# rpi4pcie.net
KiCad netlist of a schematic drawn in EAGLE
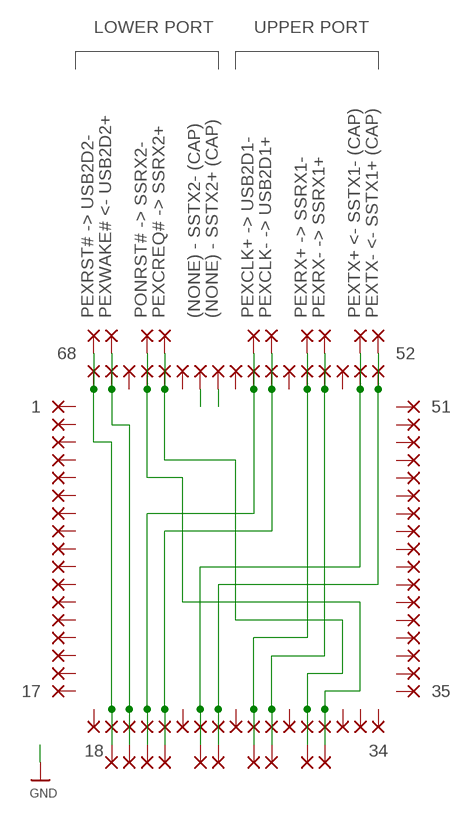
[diagram p0: schematic, sheet 1]

(export (version "E")
  (design (tool "Eeschema 10.0.6"))
  (components
    (comp (ref "PAD1")
      (value "PADQFN-0.4")
      (footprint "eagle-import:PAD-QFN-0.4")
      (libsource (lib "eagle-import") (part "PADQFN-0.4"))
    )
    (comp (ref "PAD2")
      (value "PADQFN-0.4")
      (footprint "eagle-import:PAD-QFN-0.4")
      (libsource (lib "eagle-import") (part "PADQFN-0.4"))
    )
    (comp (ref "PAD3")
      (value "PADQFN-0.4")
      (footprint "eagle-import:PAD-QFN-0.4")
      (libsource (lib "eagle-import") (part "PADQFN-0.4"))
    )
    (comp (ref "PAD4")
      (value "PADQFN-0.4")
      (footprint "eagle-import:PAD-QFN-0.4")
      (libsource (lib "eagle-import") (part "PADQFN-0.4"))
    )
    (comp (ref "PAD5")
      (value "PADQFN-0.4")
      (footprint "eagle-import:PAD-QFN-0.4")
      (libsource (lib "eagle-import") (part "PADQFN-0.4"))
    )
    (comp (ref "PAD6")
      (value "PADQFN-0.4")
      (footprint "eagle-import:PAD-QFN-0.4")
      (libsource (lib "eagle-import") (part "PADQFN-0.4"))
    )
    (comp (ref "PAD7")
      (value "PADQFN-0.4")
      (footprint "eagle-import:PAD-QFN-0.4")
      (libsource (lib "eagle-import") (part "PADQFN-0.4"))
    )
    (comp (ref "PAD8")
      (value "PADQFN-0.4")
      (footprint "eagle-import:PAD-QFN-0.4")
      (libsource (lib "eagle-import") (part "PADQFN-0.4"))
    )
    (comp (ref "PAD9")
      (value "PADQFN-0.4")
      (footprint "eagle-import:PAD-QFN-0.4")
      (libsource (lib "eagle-import") (part "PADQFN-0.4"))
    )
    (comp (ref "PAD10")
      (value "PADQFN-0.4")
      (footprint "eagle-import:PAD-QFN-0.4")
      (libsource (lib "eagle-import") (part "PADQFN-0.4"))
    )
    (comp (ref "PAD11")
      (value "PADQFN-0.4")
      (footprint "eagle-import:PAD-QFN-0.4")
      (libsource (lib "eagle-import") (part "PADQFN-0.4"))
    )
    (comp (ref "PAD12")
      (value "PADQFN-0.4")
      (footprint "eagle-import:PAD-QFN-0.4")
      (libsource (lib "eagle-import") (part "PADQFN-0.4"))
    )
    (comp (ref "PAD13")
      (value "PADQFN-0.4")
      (footprint "eagle-import:PAD-QFN-0.4")
      (libsource (lib "eagle-import") (part "PADQFN-0.4"))
    )
    (comp (ref "PAD14")
      (value "PADQFN-0.4")
      (footprint "eagle-import:PAD-QFN-0.4")
      (libsource (lib "eagle-import") (part "PADQFN-0.4"))
    )
    (comp (ref "PAD15")
      (value "PADQFN-0.4")
      (footprint "eagle-import:PAD-QFN-0.4")
      (libsource (lib "eagle-import") (part "PADQFN-0.4"))
    )
    (comp (ref "PAD16")
      (value "PADQFN-0.4")
      (footprint "eagle-import:PAD-QFN-0.4")
      (libsource (lib "eagle-import") (part "PADQFN-0.4"))
    )
    (comp (ref "PAD17")
      (value "PADQFN-0.4")
      (footprint "eagle-import:PAD-QFN-0.4")
      (libsource (lib "eagle-import") (part "PADQFN-0.4"))
    )
    (comp (ref "PAD18")
      (value "PADQFN-0.4")
      (footprint "eagle-import:PAD-QFN-0.4")
      (libsource (lib "eagle-import") (part "PADQFN-0.4"))
    )
    (comp (ref "PAD19")
      (value "PADQFN-0.4")
      (footprint "eagle-import:PAD-QFN-0.4")
      (libsource (lib "eagle-import") (part "PADQFN-0.4"))
    )
    (comp (ref "PAD20")
      (value "PADQFN-0.4")
      (footprint "eagle-import:PAD-QFN-0.4")
      (libsource (lib "eagle-import") (part "PADQFN-0.4"))
    )
    (comp (ref "PAD21")
      (value "PADQFN-0.4")
      (footprint "eagle-import:PAD-QFN-0.4")
      (libsource (lib "eagle-import") (part "PADQFN-0.4"))
    )
    (comp (ref "PAD22")
      (value "PADQFN-0.4")
      (footprint "eagle-import:PAD-QFN-0.4")
      (libsource (lib "eagle-import") (part "PADQFN-0.4"))
    )
    (comp (ref "PAD23")
      (value "PADQFN-0.4")
      (footprint "eagle-import:PAD-QFN-0.4")
      (libsource (lib "eagle-import") (part "PADQFN-0.4"))
    )
    (comp (ref "PAD24")
      (value "PADQFN-0.4")
      (footprint "eagle-import:PAD-QFN-0.4")
      (libsource (lib "eagle-import") (part "PADQFN-0.4"))
    )
    (comp (ref "PAD25")
      (value "PADQFN-0.4")
      (footprint "eagle-import:PAD-QFN-0.4")
      (libsource (lib "eagle-import") (part "PADQFN-0.4"))
    )
    (comp (ref "PAD26")
      (value "PADQFN-0.4")
      (footprint "eagle-import:PAD-QFN-0.4")
      (libsource (lib "eagle-import") (part "PADQFN-0.4"))
    )
    (comp (ref "PAD27")
      (value "PADQFN-0.4")
      (footprint "eagle-import:PAD-QFN-0.4")
      (libsource (lib "eagle-import") (part "PADQFN-0.4"))
    )
    (comp (ref "PAD28")
      (value "PADQFN-0.4")
      (footprint "eagle-import:PAD-QFN-0.4")
      (libsource (lib "eagle-import") (part "PADQFN-0.4"))
    )
    (comp (ref "PAD29")
      (value "PADQFN-0.4")
      (footprint "eagle-import:PAD-QFN-0.4")
      (libsource (lib "eagle-import") (part "PADQFN-0.4"))
    )
    (comp (ref "PAD30")
      (value "PADQFN-0.4")
      (footprint "eagle-import:PAD-QFN-0.4")
      (libsource (lib "eagle-import") (part "PADQFN-0.4"))
    )
    (comp (ref "PAD31")
      (value "PADQFN-0.4")
      (footprint "eagle-import:PAD-QFN-0.4")
      (libsource (lib "eagle-import") (part "PADQFN-0.4"))
    )
    (comp (ref "PAD32")
      (value "PADQFN-0.4")
      (footprint "eagle-import:PAD-QFN-0.4")
      (libsource (lib "eagle-import") (part "PADQFN-0.4"))
    )
    (comp (ref "PAD33")
      (value "PADQFN-0.4")
      (footprint "eagle-import:PAD-QFN-0.4")
      (libsource (lib "eagle-import") (part "PADQFN-0.4"))
    )
    (comp (ref "PAD34")
      (value "PADQFN-0.4")
      (footprint "eagle-import:PAD-QFN-0.4")
      (libsource (lib "eagle-import") (part "PADQFN-0.4"))
    )
    (comp (ref "PAD35")
      (value "PADQFN-0.4")
      (footprint "eagle-import:PAD-QFN-0.4")
      (libsource (lib "eagle-import") (part "PADQFN-0.4"))
    )
    (comp (ref "PAD36")
      (value "PADQFN-0.4")
      (footprint "eagle-import:PAD-QFN-0.4")
      (libsource (lib "eagle-import") (part "PADQFN-0.4"))
    )
    (comp (ref "PAD37")
      (value "PADQFN-0.4")
      (footprint "eagle-import:PAD-QFN-0.4")
      (libsource (lib "eagle-import") (part "PADQFN-0.4"))
    )
    (comp (ref "PAD38")
      (value "PADQFN-0.4")
      (footprint "eagle-import:PAD-QFN-0.4")
      (libsource (lib "eagle-import") (part "PADQFN-0.4"))
    )
    (comp (ref "PAD39")
      (value "PADQFN-0.4")
      (footprint "eagle-import:PAD-QFN-0.4")
      (libsource (lib "eagle-import") (part "PADQFN-0.4"))
    )
    (comp (ref "PAD40")
      (value "PADQFN-0.4")
      (footprint "eagle-import:PAD-QFN-0.4")
      (libsource (lib "eagle-import") (part "PADQFN-0.4"))
    )
    (comp (ref "PAD41")
      (value "PADQFN-0.4")
      (footprint "eagle-import:PAD-QFN-0.4")
      (libsource (lib "eagle-import") (part "PADQFN-0.4"))
    )
    (comp (ref "PAD42")
      (value "PADQFN-0.4")
      (footprint "eagle-import:PAD-QFN-0.4")
      (libsource (lib "eagle-import") (part "PADQFN-0.4"))
    )
    (comp (ref "PAD43")
      (value "PADQFN-0.4")
      (footprint "eagle-import:PAD-QFN-0.4")
      (libsource (lib "eagle-import") (part "PADQFN-0.4"))
    )
    (comp (ref "PAD44")
      (value "PADQFN-0.4")
      (footprint "eagle-import:PAD-QFN-0.4")
      (libsource (lib "eagle-import") (part "PADQFN-0.4"))
    )
    (comp (ref "PAD45")
      (value "PADQFN-0.4")
      (footprint "eagle-import:PAD-QFN-0.4")
      (libsource (lib "eagle-import") (part "PADQFN-0.4"))
    )
    (comp (ref "PAD46")
      (value "PADQFN-0.4")
      (footprint "eagle-import:PAD-QFN-0.4")
      (libsource (lib "eagle-import") (part "PADQFN-0.4"))
    )
    (comp (ref "PAD47")
      (value "PADQFN-0.4")
      (footprint "eagle-import:PAD-QFN-0.4")
      (libsource (lib "eagle-import") (part "PADQFN-0.4"))
    )
    (comp (ref "PAD48")
      (value "PADQFN-0.4")
      (footprint "eagle-import:PAD-QFN-0.4")
      (libsource (lib "eagle-import") (part "PADQFN-0.4"))
    )
    (comp (ref "PAD49")
      (value "PADQFN-0.4")
      (footprint "eagle-import:PAD-QFN-0.4")
      (libsource (lib "eagle-import") (part "PADQFN-0.4"))
    )
    (comp (ref "PAD50")
      (value "PADQFN-0.4")
      (footprint "eagle-import:PAD-QFN-0.4")
      (libsource (lib "eagle-import") (part "PADQFN-0.4"))
    )
    (comp (ref "PAD51")
      (value "PADQFN-0.4")
      (footprint "eagle-import:PAD-QFN-0.4")
      (libsource (lib "eagle-import") (part "PADQFN-0.4"))
    )
    (comp (ref "PAD52")
      (value "PADQFN-0.4")
      (footprint "eagle-import:PAD-QFN-0.4")
      (libsource (lib "eagle-import") (part "PADQFN-0.4"))
    )
    (comp (ref "PAD53")
      (value "PADQFN-0.4")
      (footprint "eagle-import:PAD-QFN-0.4")
      (libsource (lib "eagle-import") (part "PADQFN-0.4"))
    )
    (comp (ref "PAD54")
      (value "PADQFN-0.4")
      (footprint "eagle-import:PAD-QFN-0.4")
      (libsource (lib "eagle-import") (part "PADQFN-0.4"))
    )
    (comp (ref "PAD55")
      (value "PADQFN-0.4")
      (footprint "eagle-import:PAD-QFN-0.4")
      (libsource (lib "eagle-import") (part "PADQFN-0.4"))
    )
    (comp (ref "PAD56")
      (value "PADQFN-0.4")
      (footprint "eagle-import:PAD-QFN-0.4")
      (libsource (lib "eagle-import") (part "PADQFN-0.4"))
    )
    (comp (ref "PAD57")
      (value "PADQFN-0.4")
      (footprint "eagle-import:PAD-QFN-0.4")
      (libsource (lib "eagle-import") (part "PADQFN-0.4"))
    )
    (comp (ref "PAD58")
      (value "PADQFN-0.4")
      (footprint "eagle-import:PAD-QFN-0.4")
      (libsource (lib "eagle-import") (part "PADQFN-0.4"))
    )
    (comp (ref "PAD59")
      (value "PADQFN-0.4")
      (footprint "eagle-import:PAD-QFN-0.4")
      (libsource (lib "eagle-import") (part "PADQFN-0.4"))
    )
    (comp (ref "PAD60")
      (value "PADQFN-0.4")
      (footprint "eagle-import:PAD-QFN-0.4")
      (libsource (lib "eagle-import") (part "PADQFN-0.4"))
    )
    (comp (ref "PAD61")
      (value "PADQFN-0.4")
      (footprint "eagle-import:PAD-QFN-0.4")
      (libsource (lib "eagle-import") (part "PADQFN-0.4"))
    )
    (comp (ref "PAD62")
      (value "PADQFN-0.4")
      (footprint "eagle-import:PAD-QFN-0.4")
      (libsource (lib "eagle-import") (part "PADQFN-0.4"))
    )
    (comp (ref "PAD63")
      (value "PADQFN-0.4")
      (footprint "eagle-import:PAD-QFN-0.4")
      (libsource (lib "eagle-import") (part "PADQFN-0.4"))
    )
    (comp (ref "PAD64")
      (value "PADQFN-0.4")
      (footprint "eagle-import:PAD-QFN-0.4")
      (libsource (lib "eagle-import") (part "PADQFN-0.4"))
    )
    (comp (ref "PAD65")
      (value "PADQFN-0.4")
      (footprint "eagle-import:PAD-QFN-0.4")
      (libsource (lib "eagle-import") (part "PADQFN-0.4"))
    )
    (comp (ref "PAD66")
      (value "PADQFN-0.4")
      (footprint "eagle-import:PAD-QFN-0.4")
      (libsource (lib "eagle-import") (part "PADQFN-0.4"))
    )
    (comp (ref "PAD67")
      (value "PADQFN-0.4")
      (footprint "eagle-import:PAD-QFN-0.4")
      (libsource (lib "eagle-import") (part "PADQFN-0.4"))
    )
    (comp (ref "PAD68")
      (value "PADQFN-0.4")
      (footprint "eagle-import:PAD-QFN-0.4")
      (libsource (lib "eagle-import") (part "PADQFN-0.4"))
    )
    (comp (ref "PAD69")
      (value "PADQFN-0.4")
      (footprint "eagle-import:PAD-QFN-0.4")
      (libsource (lib "eagle-import") (part "PADQFN-0.4"))
    )
    (comp (ref "PAD70")
      (value "PADQFN-0.4")
      (footprint "eagle-import:PAD-QFN-0.4")
      (libsource (lib "eagle-import") (part "PADQFN-0.4"))
    )
    (comp (ref "PAD71")
      (value "PADQFN-0.4")
      (footprint "eagle-import:PAD-QFN-0.4")
      (libsource (lib "eagle-import") (part "PADQFN-0.4"))
    )
    (comp (ref "PAD72")
      (value "PADQFN-0.4")
      (footprint "eagle-import:PAD-QFN-0.4")
      (libsource (lib "eagle-import") (part "PADQFN-0.4"))
    )
    (comp (ref "PAD73")
      (value "PADQFN-0.4")
      (footprint "eagle-import:PAD-QFN-0.4")
      (libsource (lib "eagle-import") (part "PADQFN-0.4"))
    )
    (comp (ref "PAD74")
      (value "PADQFN-0.4")
      (footprint "eagle-import:PAD-QFN-0.4")
      (libsource (lib "eagle-import") (part "PADQFN-0.4"))
    )
    (comp (ref "PAD75")
      (value "PADQFN-0.4")
      (footprint "eagle-import:PAD-QFN-0.4")
      (libsource (lib "eagle-import") (part "PADQFN-0.4"))
    )
    (comp (ref "PAD76")
      (value "PADQFN-0.4")
      (footprint "eagle-import:PAD-QFN-0.4")
      (libsource (lib "eagle-import") (part "PADQFN-0.4"))
    )
    (comp (ref "PAD77")
      (value "PADQFN-0.4")
      (footprint "eagle-import:PAD-QFN-0.4")
      (libsource (lib "eagle-import") (part "PADQFN-0.4"))
    )
    (comp (ref "PAD78")
      (value "PADQFN-0.4")
      (footprint "eagle-import:PAD-QFN-0.4")
      (libsource (lib "eagle-import") (part "PADQFN-0.4"))
    )
    (comp (ref "PAD79")
      (value "PADQFN-0.4")
      (footprint "eagle-import:PAD-QFN-0.4")
      (libsource (lib "eagle-import") (part "PADQFN-0.4"))
    )
    (comp (ref "PAD80")
      (value "PADQFN-0.4")
      (footprint "eagle-import:PAD-QFN-0.4")
      (libsource (lib "eagle-import") (part "PADQFN-0.4"))
    )
    (comp (ref "PAD81")
      (value "PADQFN-0.4")
      (footprint "eagle-import:PAD-QFN-0.4")
      (libsource (lib "eagle-import") (part "PADQFN-0.4"))
    )
    (comp (ref "PAD82")
      (value "PADQFN-0.4")
      (footprint "eagle-import:PAD-QFN-0.4")
      (libsource (lib "eagle-import") (part "PADQFN-0.4"))
    )
    (comp (ref "PAD83")
      (value "PADQFN-0.4")
      (footprint "eagle-import:PAD-QFN-0.4")
      (libsource (lib "eagle-import") (part "PADQFN-0.4"))
    )
    (comp (ref "PAD84")
      (value "PADQFN-0.4")
      (footprint "eagle-import:PAD-QFN-0.4")
      (libsource (lib "eagle-import") (part "PADQFN-0.4"))
    )
    (comp (ref "PAD85")
      (value "PADQFN-0.4")
      (footprint "eagle-import:PAD-QFN-0.4")
      (libsource (lib "eagle-import") (part "PADQFN-0.4"))
    )
    (comp (ref "PAD86")
      (value "PADQFN-0.4")
      (footprint "eagle-import:PAD-QFN-0.4")
      (libsource (lib "eagle-import") (part "PADQFN-0.4"))
    )
    (comp (ref "PAD87")
      (value "PADQFN-0.4")
      (footprint "eagle-import:PAD-QFN-0.4")
      (libsource (lib "eagle-import") (part "PADQFN-0.4"))
    )
    (comp (ref "PAD88")
      (value "PADQFN-0.4")
      (footprint "eagle-import:PAD-QFN-0.4")
      (libsource (lib "eagle-import") (part "PADQFN-0.4"))
    )
  )
  (nets
    (net (code "2") (name "Net-(PAD19-P$1)") (class "Default")
      (node (ref "PAD19") (pin "1") (pinfunction "P$1_1") (pintype "passive"))
      (node (ref "PAD68") (pin "1") (pinfunction "P$1_1") (pintype "passive"))
      (node (ref "PAD69") (pin "1") (pinfunction "P$1_1") (pintype "passive"))
      (node (ref "PAD77") (pin "1") (pinfunction "P$1_1") (pintype "passive"))
    )
    (net (code "3") (name "Net-(PAD20-P$1)") (class "Default")
      (node (ref "PAD20") (pin "1") (pinfunction "P$1_1") (pintype "passive"))
      (node (ref "PAD67") (pin "1") (pinfunction "P$1_1") (pintype "passive"))
      (node (ref "PAD70") (pin "1") (pinfunction "P$1_1") (pintype "passive"))
      (node (ref "PAD78") (pin "1") (pinfunction "P$1_1") (pintype "passive"))
    )
    (net (code "4") (name "Net-(PAD21-P$1)") (class "Default")
      (node (ref "PAD21") (pin "1") (pinfunction "P$1_1") (pintype "passive"))
      (node (ref "PAD59") (pin "1") (pinfunction "P$1_1") (pintype "passive"))
      (node (ref "PAD71") (pin "1") (pinfunction "P$1_1") (pintype "passive"))
      (node (ref "PAD79") (pin "1") (pinfunction "P$1_1") (pintype "passive"))
    )
    (net (code "5") (name "Net-(PAD22-P$1)") (class "Default")
      (node (ref "PAD22") (pin "1") (pinfunction "P$1_1") (pintype "passive"))
      (node (ref "PAD58") (pin "1") (pinfunction "P$1_1") (pintype "passive"))
      (node (ref "PAD72") (pin "1") (pinfunction "P$1_1") (pintype "passive"))
      (node (ref "PAD80") (pin "1") (pinfunction "P$1_1") (pintype "passive"))
    )
    (net (code "6") (name "Net-(PAD24-P$1)") (class "Default")
      (node (ref "PAD24") (pin "1") (pinfunction "P$1_1") (pintype "passive"))
      (node (ref "PAD53") (pin "1") (pinfunction "P$1_1") (pintype "passive"))
      (node (ref "PAD75") (pin "1") (pinfunction "P$1_1") (pintype "passive"))
      (node (ref "PAD81") (pin "1") (pinfunction "P$1_1") (pintype "passive"))
    )
    (net (code "7") (name "Net-(PAD25-P$1)") (class "Default")
      (node (ref "PAD25") (pin "1") (pinfunction "P$1_1") (pintype "passive"))
      (node (ref "PAD52") (pin "1") (pinfunction "P$1_1") (pintype "passive"))
      (node (ref "PAD76") (pin "1") (pinfunction "P$1_1") (pintype "passive"))
      (node (ref "PAD82") (pin "1") (pinfunction "P$1_1") (pintype "passive"))
    )
    (net (code "8") (name "Net-(PAD27-P$1)") (class "Default")
      (node (ref "PAD27") (pin "1") (pinfunction "P$1_1") (pintype "passive"))
      (node (ref "PAD56") (pin "1") (pinfunction "P$1_1") (pintype "passive"))
      (node (ref "PAD73") (pin "1") (pinfunction "P$1_1") (pintype "passive"))
      (node (ref "PAD83") (pin "1") (pinfunction "P$1_1") (pintype "passive"))
    )
    (net (code "9") (name "Net-(PAD28-P$1)") (class "Default")
      (node (ref "PAD28") (pin "1") (pinfunction "P$1_1") (pintype "passive"))
      (node (ref "PAD55") (pin "1") (pinfunction "P$1_1") (pintype "passive"))
      (node (ref "PAD74") (pin "1") (pinfunction "P$1_1") (pintype "passive"))
      (node (ref "PAD84") (pin "1") (pinfunction "P$1_1") (pintype "passive"))
    )
    (net (code "10") (name "Net-(PAD30-P$1)") (class "Default")
      (node (ref "PAD30") (pin "1") (pinfunction "P$1_1") (pintype "passive"))
      (node (ref "PAD64") (pin "1") (pinfunction "P$1_1") (pintype "passive"))
      (node (ref "PAD85") (pin "1") (pinfunction "P$1_1") (pintype "passive"))
      (node (ref "PAD88") (pin "1") (pinfunction "P$1_1") (pintype "passive"))
    )
    (net (code "11") (name "Net-(PAD31-P$1)") (class "Default")
      (node (ref "PAD31") (pin "1") (pinfunction "P$1_1") (pintype "passive"))
      (node (ref "PAD65") (pin "1") (pinfunction "P$1_1") (pintype "passive"))
      (node (ref "PAD86") (pin "1") (pinfunction "P$1_1") (pintype "passive"))
      (node (ref "PAD87") (pin "1") (pinfunction "P$1_1") (pintype "passive"))
    )
    (net (code "12") (name "unconnected-(PAD1-P$1-Pad1)") (class "Default")
      (node (ref "PAD1") (pin "1") (pinfunction "P$1_1") (pintype "passive"))
    )
    (net (code "13") (name "unconnected-(PAD2-P$1-Pad1)") (class "Default")
      (node (ref "PAD2") (pin "1") (pinfunction "P$1_1") (pintype "passive"))
    )
    (net (code "14") (name "unconnected-(PAD3-P$1-Pad1)") (class "Default")
      (node (ref "PAD3") (pin "1") (pinfunction "P$1_1") (pintype "passive"))
    )
    (net (code "15") (name "unconnected-(PAD4-P$1-Pad1)") (class "Default")
      (node (ref "PAD4") (pin "1") (pinfunction "P$1_1") (pintype "passive"))
    )
    (net (code "16") (name "unconnected-(PAD5-P$1-Pad1)") (class "Default")
      (node (ref "PAD5") (pin "1") (pinfunction "P$1_1") (pintype "passive"))
    )
    (net (code "17") (name "unconnected-(PAD6-P$1-Pad1)") (class "Default")
      (node (ref "PAD6") (pin "1") (pinfunction "P$1_1") (pintype "passive"))
    )
    (net (code "18") (name "unconnected-(PAD7-P$1-Pad1)") (class "Default")
      (node (ref "PAD7") (pin "1") (pinfunction "P$1_1") (pintype "passive"))
    )
    (net (code "19") (name "unconnected-(PAD8-P$1-Pad1)") (class "Default")
      (node (ref "PAD8") (pin "1") (pinfunction "P$1_1") (pintype "passive"))
    )
    (net (code "20") (name "unconnected-(PAD9-P$1-Pad1)") (class "Default")
      (node (ref "PAD9") (pin "1") (pinfunction "P$1_1") (pintype "passive"))
    )
    (net (code "21") (name "unconnected-(PAD10-P$1-Pad1)") (class "Default")
      (node (ref "PAD10") (pin "1") (pinfunction "P$1_1") (pintype "passive"))
    )
    (net (code "22") (name "unconnected-(PAD11-P$1-Pad1)") (class "Default")
      (node (ref "PAD11") (pin "1") (pinfunction "P$1_1") (pintype "passive"))
    )
    (net (code "23") (name "unconnected-(PAD12-P$1-Pad1)") (class "Default")
      (node (ref "PAD12") (pin "1") (pinfunction "P$1_1") (pintype "passive"))
    )
    (net (code "24") (name "unconnected-(PAD13-P$1-Pad1)") (class "Default")
      (node (ref "PAD13") (pin "1") (pinfunction "P$1_1") (pintype "passive"))
    )
    (net (code "25") (name "unconnected-(PAD14-P$1-Pad1)") (class "Default")
      (node (ref "PAD14") (pin "1") (pinfunction "P$1_1") (pintype "passive"))
    )
    (net (code "26") (name "unconnected-(PAD15-P$1-Pad1)") (class "Default")
      (node (ref "PAD15") (pin "1") (pinfunction "P$1_1") (pintype "passive"))
    )
    (net (code "27") (name "unconnected-(PAD16-P$1-Pad1)") (class "Default")
      (node (ref "PAD16") (pin "1") (pinfunction "P$1_1") (pintype "passive"))
    )
    (net (code "28") (name "unconnected-(PAD17-P$1-Pad1)") (class "Default")
      (node (ref "PAD17") (pin "1") (pinfunction "P$1_1") (pintype "passive"))
    )
    (net (code "29") (name "unconnected-(PAD18-P$1-Pad1)") (class "Default")
      (node (ref "PAD18") (pin "1") (pinfunction "P$1_1") (pintype "passive"))
    )
    (net (code "30") (name "unconnected-(PAD23-P$1-Pad1)") (class "Default")
      (node (ref "PAD23") (pin "1") (pinfunction "P$1_1") (pintype "passive"))
    )
    (net (code "31") (name "unconnected-(PAD26-P$1-Pad1)") (class "Default")
      (node (ref "PAD26") (pin "1") (pinfunction "P$1_1") (pintype "passive"))
    )
    (net (code "32") (name "unconnected-(PAD29-P$1-Pad1)") (class "Default")
      (node (ref "PAD29") (pin "1") (pinfunction "P$1_1") (pintype "passive"))
    )
    (net (code "33") (name "unconnected-(PAD32-P$1-Pad1)") (class "Default")
      (node (ref "PAD32") (pin "1") (pinfunction "P$1_1") (pintype "passive"))
    )
    (net (code "34") (name "unconnected-(PAD33-P$1-Pad1)") (class "Default")
      (node (ref "PAD33") (pin "1") (pinfunction "P$1_1") (pintype "passive"))
    )
    (net (code "35") (name "unconnected-(PAD34-P$1-Pad1)") (class "Default")
      (node (ref "PAD34") (pin "1") (pinfunction "P$1_1") (pintype "passive"))
    )
    (net (code "36") (name "unconnected-(PAD35-P$1-Pad1)") (class "Default")
      (node (ref "PAD35") (pin "1") (pinfunction "P$1_1") (pintype "passive"))
    )
    (net (code "37") (name "unconnected-(PAD36-P$1-Pad1)") (class "Default")
      (node (ref "PAD36") (pin "1") (pinfunction "P$1_1") (pintype "passive"))
    )
    (net (code "38") (name "unconnected-(PAD37-P$1-Pad1)") (class "Default")
      (node (ref "PAD37") (pin "1") (pinfunction "P$1_1") (pintype "passive"))
    )
    (net (code "39") (name "unconnected-(PAD38-P$1-Pad1)") (class "Default")
      (node (ref "PAD38") (pin "1") (pinfunction "P$1_1") (pintype "passive"))
    )
    (net (code "40") (name "unconnected-(PAD39-P$1-Pad1)") (class "Default")
      (node (ref "PAD39") (pin "1") (pinfunction "P$1_1") (pintype "passive"))
    )
    (net (code "41") (name "unconnected-(PAD40-P$1-Pad1)") (class "Default")
      (node (ref "PAD40") (pin "1") (pinfunction "P$1_1") (pintype "passive"))
    )
    (net (code "42") (name "unconnected-(PAD41-P$1-Pad1)") (class "Default")
      (node (ref "PAD41") (pin "1") (pinfunction "P$1_1") (pintype "passive"))
    )
    (net (code "43") (name "unconnected-(PAD42-P$1-Pad1)") (class "Default")
      (node (ref "PAD42") (pin "1") (pinfunction "P$1_1") (pintype "passive"))
    )
    (net (code "44") (name "unconnected-(PAD43-P$1-Pad1)") (class "Default")
      (node (ref "PAD43") (pin "1") (pinfunction "P$1_1") (pintype "passive"))
    )
    (net (code "45") (name "unconnected-(PAD44-P$1-Pad1)") (class "Default")
      (node (ref "PAD44") (pin "1") (pinfunction "P$1_1") (pintype "passive"))
    )
    (net (code "46") (name "unconnected-(PAD45-P$1-Pad1)") (class "Default")
      (node (ref "PAD45") (pin "1") (pinfunction "P$1_1") (pintype "passive"))
    )
    (net (code "47") (name "unconnected-(PAD46-P$1-Pad1)") (class "Default")
      (node (ref "PAD46") (pin "1") (pinfunction "P$1_1") (pintype "passive"))
    )
    (net (code "48") (name "unconnected-(PAD47-P$1-Pad1)") (class "Default")
      (node (ref "PAD47") (pin "1") (pinfunction "P$1_1") (pintype "passive"))
    )
    (net (code "49") (name "unconnected-(PAD48-P$1-Pad1)") (class "Default")
      (node (ref "PAD48") (pin "1") (pinfunction "P$1_1") (pintype "passive"))
    )
    (net (code "50") (name "unconnected-(PAD49-P$1-Pad1)") (class "Default")
      (node (ref "PAD49") (pin "1") (pinfunction "P$1_1") (pintype "passive"))
    )
    (net (code "51") (name "unconnected-(PAD50-P$1-Pad1)") (class "Default")
      (node (ref "PAD50") (pin "1") (pinfunction "P$1_1") (pintype "passive"))
    )
    (net (code "52") (name "unconnected-(PAD51-P$1-Pad1)") (class "Default")
      (node (ref "PAD51") (pin "1") (pinfunction "P$1_1") (pintype "passive"))
    )
    (net (code "53") (name "unconnected-(PAD54-P$1-Pad1)") (class "Default")
      (node (ref "PAD54") (pin "1") (pinfunction "P$1_1") (pintype "passive"))
    )
    (net (code "54") (name "unconnected-(PAD57-P$1-Pad1)") (class "Default")
      (node (ref "PAD57") (pin "1") (pinfunction "P$1_1") (pintype "passive"))
    )
    (net (code "55") (name "unconnected-(PAD60-P$1-Pad1)") (class "Default")
      (node (ref "PAD60") (pin "1") (pinfunction "P$1_1") (pintype "passive"))
    )
    (net (code "56") (name "unconnected-(PAD61-P$1-Pad1)") (class "Default")
      (node (ref "PAD61") (pin "1") (pinfunction "P$1_1") (pintype "passive"))
    )
    (net (code "57") (name "unconnected-(PAD62-P$1-Pad1)") (class "Default")
      (node (ref "PAD62") (pin "1") (pinfunction "P$1_1") (pintype "passive"))
    )
    (net (code "58") (name "unconnected-(PAD63-P$1-Pad1)") (class "Default")
      (node (ref "PAD63") (pin "1") (pinfunction "P$1_1") (pintype "passive"))
    )
    (net (code "59") (name "unconnected-(PAD66-P$1-Pad1)") (class "Default")
      (node (ref "PAD66") (pin "1") (pinfunction "P$1_1") (pintype "passive"))
    )
  )
)
